# ShoulderDriverChannel.net
KiCad netlist of a schematic drawn in Altium Designer
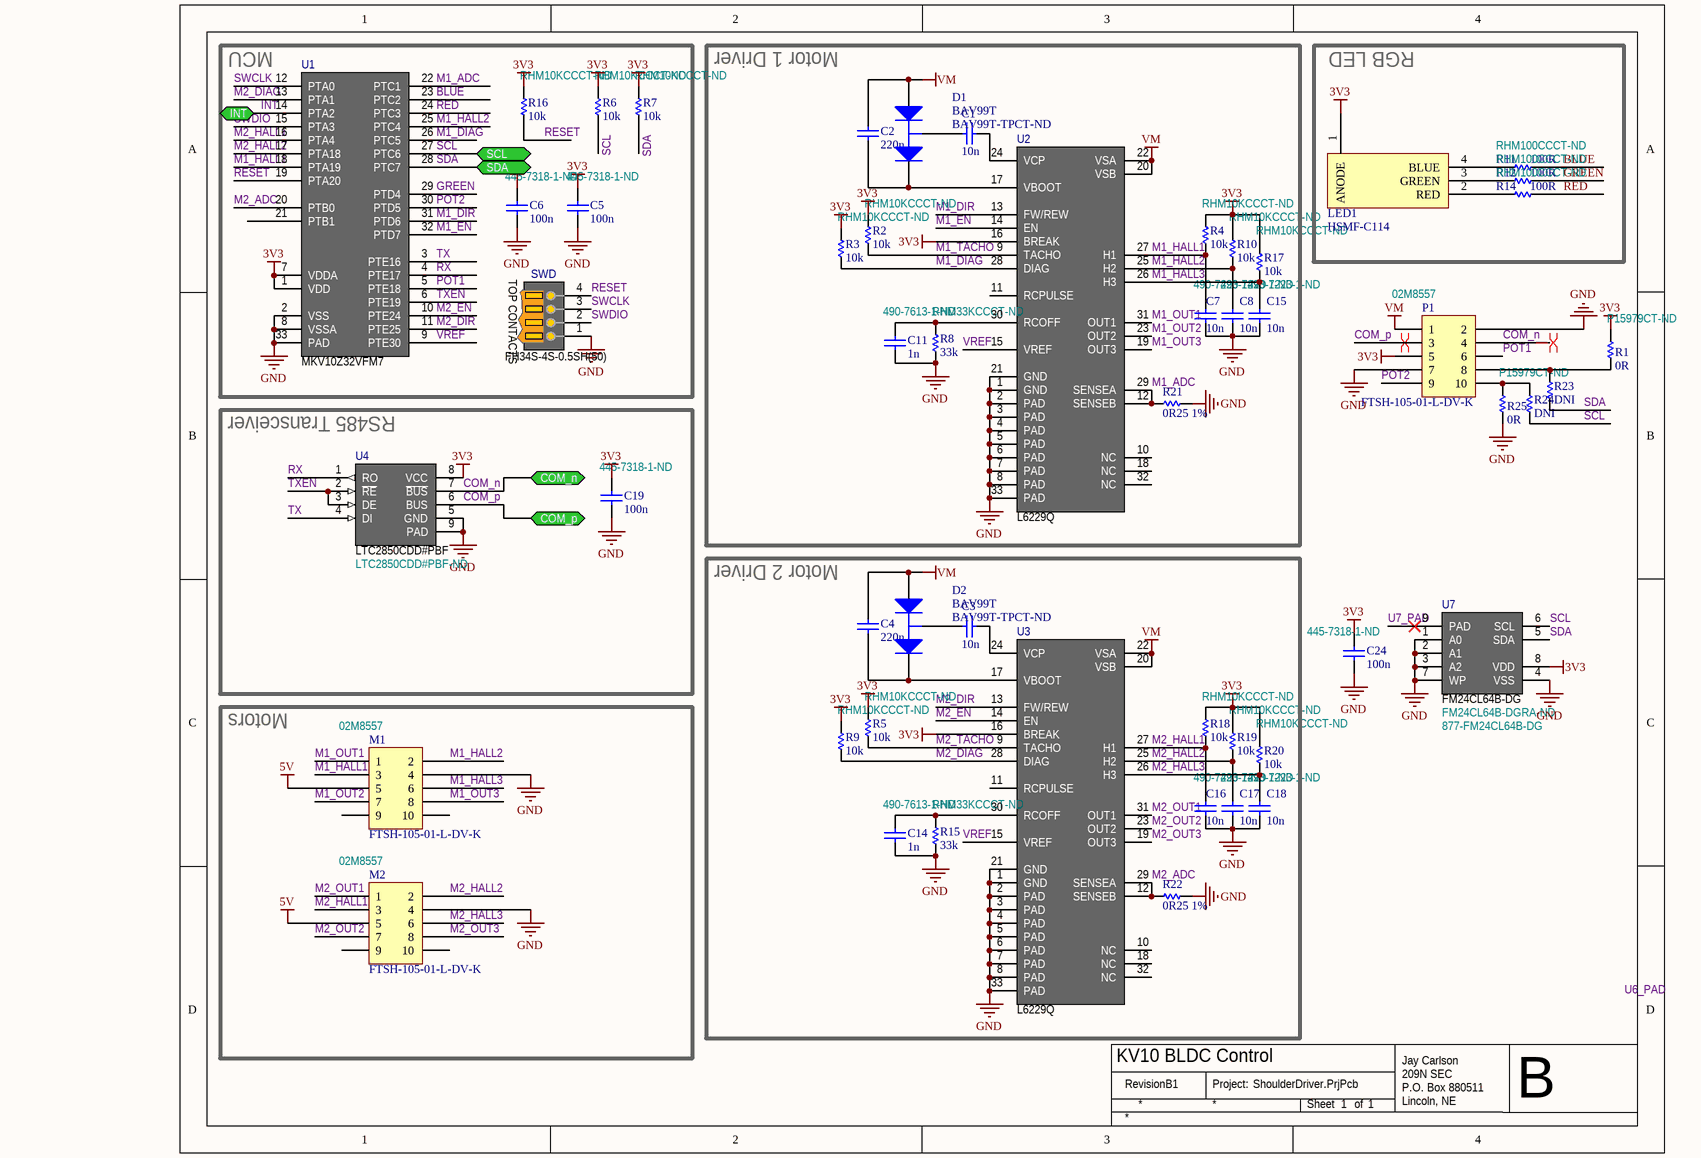
[diagram p0: ShoulderDriverChannel.SchDoc]

(export (version "E")
  (design (tool "Eeschema 10.0.6"))
  (components
    (comp (ref "C1")
      (value "10n")
      (footprint "CAPC1005N")
      (description "Capacitor (Semiconductor SIM Model)")
      (fields (field (name "PUBLISHER") "Altium Limited"))
      (libsource (lib "Miscellaneous Devices") (part "Cap Semi"))
    )
    (comp (ref "C2")
      (value "220n")
      (footprint "CAPC1005N")
      (description "Capacitor (Semiconductor SIM Model)")
      (fields (field (name "PUBLISHER") "Altium Limited"))
      (libsource (lib "Miscellaneous Devices") (part "Cap Semi"))
    )
    (comp (ref "C3")
      (value "10n")
      (footprint "CAPC1005N")
      (description "Capacitor (Semiconductor SIM Model)")
      (fields (field (name "PUBLISHER") "Altium Limited"))
      (libsource (lib "Miscellaneous Devices") (part "Cap Semi"))
    )
    (comp (ref "C4")
      (value "220n")
      (footprint "CAPC1005N")
      (description "Capacitor (Semiconductor SIM Model)")
      (fields (field (name "PUBLISHER") "Altium Limited"))
      (libsource (lib "Miscellaneous Devices") (part "Cap Semi"))
    )
    (comp (ref "C5")
      (value "100n")
      (footprint "CAPC0603N")
      (description "Capacitor (Semiconductor SIM Model)")
      (fields
        (field (name "SUPPLIER PART NUMBER 1") "445-7318-1-ND")
        (field (name "PUBLISHER") "Altium Limited")
      )
      (libsource (lib "Miscellaneous Devices") (part "Cap Semi"))
    )
    (comp (ref "C6")
      (value "100n")
      (footprint "CAPC0603N")
      (description "Capacitor (Semiconductor SIM Model)")
      (fields
        (field (name "SUPPLIER PART NUMBER 1") "445-7318-1-ND")
        (field (name "PUBLISHER") "Altium Limited")
      )
      (libsource (lib "Miscellaneous Devices") (part "Cap Semi"))
    )
    (comp (ref "C7")
      (value "10n")
      (footprint "CAPC0603N")
      (description "Capacitor (Semiconductor SIM Model)")
      (fields
        (field (name "SUPPLIER PART NUMBER 1") "490-7223-1-ND")
        (field (name "PUBLISHER") "Altium Limited")
      )
      (libsource (lib "Miscellaneous Devices") (part "Cap Semi"))
    )
    (comp (ref "C8")
      (value "10n")
      (footprint "CAPC0603N")
      (description "Capacitor (Semiconductor SIM Model)")
      (fields
        (field (name "SUPPLIER PART NUMBER 1") "490-7223-1-ND")
        (field (name "PUBLISHER") "Altium Limited")
      )
      (libsource (lib "Miscellaneous Devices") (part "Cap Semi"))
    )
    (comp (ref "C11")
      (value "1n")
      (footprint "CAPC0603N")
      (description "Capacitor (Semiconductor SIM Model)")
      (fields
        (field (name "SUPPLIER PART NUMBER 1") "490-7613-1-ND")
        (field (name "PUBLISHER") "Altium Limited")
      )
      (libsource (lib "Miscellaneous Devices") (part "Cap Semi"))
    )
    (comp (ref "C14")
      (value "1n")
      (footprint "CAPC0603N")
      (description "Capacitor (Semiconductor SIM Model)")
      (fields
        (field (name "SUPPLIER PART NUMBER 1") "490-7613-1-ND")
        (field (name "PUBLISHER") "Altium Limited")
      )
      (libsource (lib "Miscellaneous Devices") (part "Cap Semi"))
    )
    (comp (ref "C15")
      (value "10n")
      (footprint "CAPC0603N")
      (description "Capacitor (Semiconductor SIM Model)")
      (fields
        (field (name "SUPPLIER PART NUMBER 1") "490-7223-1-ND")
        (field (name "PUBLISHER") "Altium Limited")
      )
      (libsource (lib "Miscellaneous Devices") (part "Cap Semi"))
    )
    (comp (ref "C16")
      (value "10n")
      (footprint "CAPC0603N")
      (description "Capacitor (Semiconductor SIM Model)")
      (fields
        (field (name "SUPPLIER PART NUMBER 1") "490-7223-1-ND")
        (field (name "PUBLISHER") "Altium Limited")
      )
      (libsource (lib "Miscellaneous Devices") (part "Cap Semi"))
    )
    (comp (ref "C17")
      (value "10n")
      (footprint "CAPC0603N")
      (description "Capacitor (Semiconductor SIM Model)")
      (fields
        (field (name "SUPPLIER PART NUMBER 1") "490-7223-1-ND")
        (field (name "PUBLISHER") "Altium Limited")
      )
      (libsource (lib "Miscellaneous Devices") (part "Cap Semi"))
    )
    (comp (ref "C18")
      (value "10n")
      (footprint "CAPC0603N")
      (description "Capacitor (Semiconductor SIM Model)")
      (fields
        (field (name "SUPPLIER PART NUMBER 1") "490-7223-1-ND")
        (field (name "PUBLISHER") "Altium Limited")
      )
      (libsource (lib "Miscellaneous Devices") (part "Cap Semi"))
    )
    (comp (ref "C19")
      (value "100n")
      (footprint "CAPC0603N")
      (description "Capacitor (Semiconductor SIM Model)")
      (fields
        (field (name "SUPPLIER PART NUMBER 1") "445-7318-1-ND")
        (field (name "PUBLISHER") "Altium Limited")
      )
      (libsource (lib "Miscellaneous Devices") (part "Cap Semi"))
    )
    (comp (ref "C24")
      (value "100n")
      (footprint "CAPC0603N")
      (description "Capacitor (Semiconductor SIM Model)")
      (fields
        (field (name "SUPPLIER PART NUMBER 1") "445-7318-1-ND")
        (field (name "PUBLISHER") "Altium Limited")
      )
      (libsource (lib "Miscellaneous Devices") (part "Cap Semi"))
    )
    (comp (ref "D1")
      (value "BAV99T")
      (footprint "SOT-523 (SC-75)")
      (description "Silicon Switching Diode for High-Speed Switching")
      (fields
        (field (name "SUPPLIER PART NUMBER 1") "BAV99T-TPCT-ND")
        (field (name "PUBLISHER") "Altium Limited")
      )
      (libsource (lib "Infineon Discrete Diode") (part "BAV99T"))
    )
    (comp (ref "D2")
      (value "BAV99T")
      (footprint "SOT-523 (SC-75)")
      (description "Silicon Switching Diode for High-Speed Switching")
      (fields
        (field (name "SUPPLIER PART NUMBER 1") "BAV99T-TPCT-ND")
        (field (name "PUBLISHER") "Altium Limited")
      )
      (libsource (lib "Infineon Discrete Diode") (part "BAV99T"))
    )
    (comp (ref "LED1")
      (value "HSMF-C114")
      (footprint "HSMF-C114")
      (description "LED CHIP RGB 1.6X1.5X0.35MM SMD")
      (fields (field (name "MANUFACTURER") "Avago Technologies US Inc."))
      (libsource (lib "components") (part "HSMF-C114"))
    )
    (comp (ref "M1")
      (value "FTSH-105-01-L-DV-K")
      (footprint "FTSH-105-01-L-DV-K")
      (description "Header, 5-Pin, Dual row")
      (fields (field (name "SUPPLIER PART NUMBER 1") "02M8557") (field (name "PUBLISHER") "Altium Limited"))
      (libsource (lib "Miscellaneous Connectors") (part "MHDR2X5"))
    )
    (comp (ref "M2")
      (value "FTSH-105-01-L-DV-K")
      (footprint "FTSH-105-01-L-DV-K")
      (description "Header, 5-Pin, Dual row")
      (fields (field (name "SUPPLIER PART NUMBER 1") "02M8557") (field (name "PUBLISHER") "Altium Limited"))
      (libsource (lib "Miscellaneous Connectors") (part "MHDR2X5"))
    )
    (comp (ref "P1")
      (value "FTSH-105-01-L-DV-K")
      (footprint "FTSH-105-01-L-DV-K")
      (description "Header, 5-Pin, Dual row")
      (fields (field (name "SUPPLIER PART NUMBER 1") "02M8557") (field (name "PUBLISHER") "Altium Limited"))
      (libsource (lib "Miscellaneous Connectors") (part "MHDR2X5"))
    )
    (comp (ref "R1")
      (value "0R")
      (footprint "RESC0603N")
      (description "Semiconductor Resistor")
      (fields
        (field (name "SUPPLIER PART NUMBER 1") "P15979CT-ND")
        (field (name "PUBLISHER") "Altium Limited")
      )
      (libsource (lib "Miscellaneous Devices") (part "Res Semi"))
    )
    (comp (ref "R2")
      (value "10k")
      (footprint "RESC0603N")
      (description "Semiconductor Resistor")
      (fields
        (field (name "SUPPLIER PART NUMBER 1") "RHM10KCCCT-ND")
        (field (name "PUBLISHER") "Altium Limited")
      )
      (libsource (lib "Miscellaneous Devices") (part "Res Semi"))
    )
    (comp (ref "R3")
      (value "10k")
      (footprint "RESC0603N")
      (description "Semiconductor Resistor")
      (fields
        (field (name "SUPPLIER PART NUMBER 1") "RHM10KCCCT-ND")
        (field (name "PUBLISHER") "Altium Limited")
      )
      (libsource (lib "Miscellaneous Devices") (part "Res Semi"))
    )
    (comp (ref "R4")
      (value "10k")
      (footprint "RESC0603N")
      (description "Semiconductor Resistor")
      (fields
        (field (name "SUPPLIER PART NUMBER 1") "RHM10KCCCT-ND")
        (field (name "PUBLISHER") "Altium Limited")
      )
      (libsource (lib "Miscellaneous Devices") (part "Res Semi"))
    )
    (comp (ref "R5")
      (value "10k")
      (footprint "RESC0603N")
      (description "Semiconductor Resistor")
      (fields
        (field (name "SUPPLIER PART NUMBER 1") "RHM10KCCCT-ND")
        (field (name "PUBLISHER") "Altium Limited")
      )
      (libsource (lib "Miscellaneous Devices") (part "Res Semi"))
    )
    (comp (ref "R6")
      (value "10k")
      (footprint "RESC0603N")
      (description "Semiconductor Resistor")
      (fields
        (field (name "SUPPLIER PART NUMBER 1") "RHM10KCCCT-ND")
        (field (name "PUBLISHER") "Altium Limited")
      )
      (libsource (lib "Miscellaneous Devices") (part "Res Semi"))
    )
    (comp (ref "R7")
      (value "10k")
      (footprint "RESC0603N")
      (description "Semiconductor Resistor")
      (fields
        (field (name "SUPPLIER PART NUMBER 1") "RHM10KCCCT-ND")
        (field (name "PUBLISHER") "Altium Limited")
      )
      (libsource (lib "Miscellaneous Devices") (part "Res Semi"))
    )
    (comp (ref "R8")
      (value "33k")
      (footprint "RESC0603N")
      (description "Semiconductor Resistor")
      (fields
        (field (name "SUPPLIER PART NUMBER 1") "RHM33KCCCT-ND")
        (field (name "PUBLISHER") "Altium Limited")
      )
      (libsource (lib "Miscellaneous Devices") (part "Res Semi"))
    )
    (comp (ref "R9")
      (value "10k")
      (footprint "RESC0603N")
      (description "Semiconductor Resistor")
      (fields
        (field (name "SUPPLIER PART NUMBER 1") "RHM10KCCCT-ND")
        (field (name "PUBLISHER") "Altium Limited")
      )
      (libsource (lib "Miscellaneous Devices") (part "Res Semi"))
    )
    (comp (ref "R10")
      (value "10k")
      (footprint "RESC0603N")
      (description "Semiconductor Resistor")
      (fields
        (field (name "SUPPLIER PART NUMBER 1") "RHM10KCCCT-ND")
        (field (name "PUBLISHER") "Altium Limited")
      )
      (libsource (lib "Miscellaneous Devices") (part "Res Semi"))
    )
    (comp (ref "R11")
      (value "100R")
      (footprint "RESC0603N")
      (description "Semiconductor Resistor")
      (fields
        (field (name "SUPPLIER PART NUMBER 1") "RHM100CCCT-ND")
        (field (name "PUBLISHER") "Altium Limited")
      )
      (libsource (lib "Miscellaneous Devices") (part "Res Semi"))
    )
    (comp (ref "R12")
      (value "100R")
      (footprint "RESC0603N")
      (description "Semiconductor Resistor")
      (fields
        (field (name "SUPPLIER PART NUMBER 1") "RHM100CCCT-ND")
        (field (name "PUBLISHER") "Altium Limited")
      )
      (libsource (lib "Miscellaneous Devices") (part "Res Semi"))
    )
    (comp (ref "R14")
      (value "100R")
      (footprint "RESC0603N")
      (description "Semiconductor Resistor")
      (fields
        (field (name "SUPPLIER PART NUMBER 1") "RHM100CCCT-ND")
        (field (name "PUBLISHER") "Altium Limited")
      )
      (libsource (lib "Miscellaneous Devices") (part "Res Semi"))
    )
    (comp (ref "R15")
      (value "33k")
      (footprint "RESC0603N")
      (description "Semiconductor Resistor")
      (fields
        (field (name "SUPPLIER PART NUMBER 1") "RHM33KCCCT-ND")
        (field (name "PUBLISHER") "Altium Limited")
      )
      (libsource (lib "Miscellaneous Devices") (part "Res Semi"))
    )
    (comp (ref "R16")
      (value "10k")
      (footprint "RESC0603N")
      (description "Semiconductor Resistor")
      (fields
        (field (name "SUPPLIER PART NUMBER 1") "RHM10KCCCT-ND")
        (field (name "PUBLISHER") "Altium Limited")
      )
      (libsource (lib "Miscellaneous Devices") (part "Res Semi"))
    )
    (comp (ref "R17")
      (value "10k")
      (footprint "RESC0603N")
      (description "Semiconductor Resistor")
      (fields
        (field (name "SUPPLIER PART NUMBER 1") "RHM10KCCCT-ND")
        (field (name "PUBLISHER") "Altium Limited")
      )
      (libsource (lib "Miscellaneous Devices") (part "Res Semi"))
    )
    (comp (ref "R18")
      (value "10k")
      (footprint "RESC0603N")
      (description "Semiconductor Resistor")
      (fields
        (field (name "SUPPLIER PART NUMBER 1") "RHM10KCCCT-ND")
        (field (name "PUBLISHER") "Altium Limited")
      )
      (libsource (lib "Miscellaneous Devices") (part "Res Semi"))
    )
    (comp (ref "R19")
      (value "10k")
      (footprint "RESC0603N")
      (description "Semiconductor Resistor")
      (fields
        (field (name "SUPPLIER PART NUMBER 1") "RHM10KCCCT-ND")
        (field (name "PUBLISHER") "Altium Limited")
      )
      (libsource (lib "Miscellaneous Devices") (part "Res Semi"))
    )
    (comp (ref "R20")
      (value "10k")
      (footprint "RESC0603N")
      (description "Semiconductor Resistor")
      (fields
        (field (name "SUPPLIER PART NUMBER 1") "RHM10KCCCT-ND")
        (field (name "PUBLISHER") "Altium Limited")
      )
      (libsource (lib "Miscellaneous Devices") (part "Res Semi"))
    )
    (comp (ref "R21")
      (value "0R25 1%")
      (footprint "RESC1608N")
      (description "Semiconductor Resistor")
      (fields (field (name "PUBLISHER") "Altium Limited"))
      (libsource (lib "Miscellaneous Devices") (part "Res Semi"))
    )
    (comp (ref "R22")
      (value "0R25 1%")
      (footprint "RESC1608N")
      (description "Semiconductor Resistor")
      (fields (field (name "PUBLISHER") "Altium Limited"))
      (libsource (lib "Miscellaneous Devices") (part "Res Semi"))
    )
    (comp (ref "R23")
      (value "DNI")
      (footprint "RESC0603N")
      (description "Semiconductor Resistor")
      (fields (field (name "PUBLISHER") "Altium Limited"))
      (libsource (lib "Miscellaneous Devices") (part "Res Semi"))
    )
    (comp (ref "R24")
      (value "DNI")
      (footprint "RESC0603N")
      (description "Semiconductor Resistor")
      (fields (field (name "PUBLISHER") "Altium Limited"))
      (libsource (lib "Miscellaneous Devices") (part "Res Semi"))
    )
    (comp (ref "R25")
      (value "0R")
      (footprint "RESC0603N")
      (description "Semiconductor Resistor")
      (fields
        (field (name "SUPPLIER PART NUMBER 1") "P15979CT-ND")
        (field (name "PUBLISHER") "Altium Limited")
      )
      (libsource (lib "Miscellaneous Devices") (part "Res Semi"))
    )
    (comp (ref "SWD")
      (value "FH34S-4S-0.5SH(50)")
      (footprint "FH34S-4S-0.5SH(50)")
      (description "CONN FPC/FFC 4POS .5MM SMD GOLD")
      (fields (field (name "MANUFACTURER") "Hirose Electric Co Ltd"))
      (libsource (lib "FH34 series") (part "FH34S-4S-0.5SH(50)"))
    )
    (comp (ref "U1")
      (value "MKV10Z32VFM7")
      (footprint "QFN50P500X500-32V2N")
      (description "Kinetis Cortex-M0+75 MHz Motor Control 32QFN")
      (fields (field (name "MANUFACTURER") "Freescale Semiconductor"))
      (libsource (lib "Freescale K-Series ARM Microcontroller") (part "MKV10Z32VFM7"))
    )
    (comp (ref "U2")
      (value "L6229Q")
      (footprint "L6229Q")
      (description "IC MOTOR DRIVER PAR 32VFQFPN")
      (fields
        (field (name "MANUFACTURER") "STMicroelectronics")
        (field (name "MANUFACTURER PART NUMBER") "L6229QTR")
      )
      (libsource (lib "ST Motor Driver") (part "L6229Q"))
    )
    (comp (ref "U3")
      (value "L6229Q")
      (footprint "L6229Q")
      (description "IC MOTOR DRIVER PAR 32VFQFPN")
      (fields
        (field (name "MANUFACTURER") "STMicroelectronics")
        (field (name "MANUFACTURER PART NUMBER") "L6229QTR")
      )
      (libsource (lib "ST Motor Driver") (part "L6229Q"))
    )
    (comp (ref "U4")
      (value "LTC2850CDD#PBF")
      (footprint "DFN50P300X300X75-8N")
      (description "IC TXRX RS485 20MBPS 8-DFN")
      (fields
        (field (name "MANUFACTURER") "Linear Technology")
        (field (name "MANUFACTURER PART NUMBER") "LTC2850CMS8#PBF")
        (field (name "SUPPLIER PART NUMBER 1") "LTC2850CDD#PBF-ND")
      )
      (libsource (lib "LTC Transceiver") (part "LTC2850CDD#PBF"))
    )
    (comp (ref "U7")
      (value "FM24CL64B-DG")
      (footprint "DFN95P400X445X80_HS-9N")
      (description "IC FRAM 64KBIT 1MHZ 8TDFN")
      (fields
        (field (name "MANUFACTURER") "Cypress Semiconductor Corp")
        (field (name "SUPPLIER PART NUMBER 1") "FM24CL64B-DGRA-ND")
        (field (name "SUPPLIER PART NUMBER 2") "877-FM24CL64B-DG")
      )
      (libsource (lib "Cypress FRAM") (part "FM24CL64B-DG"))
    )
  )
  (nets
    (net (code "1") (name "/BLUE") (class "Default")
      (node (ref "R11") (pin "1") (pinfunction "1_1") (pintype "passive"))
      (node (ref "U1") (pin "23") (pinfunction "PTC2_23") (pintype "passive"))
    )
    (net (code "2") (name "/COM_n") (class "Default")
      (node (ref "P1") (pin "4") (pinfunction "4_4") (pintype "passive"))
      (node (ref "U4") (pin "7") (pinfunction "~{BUS}_7") (pintype "power_in"))
    )
    (net (code "3") (name "/COM_p") (class "Default")
      (node (ref "P1") (pin "3") (pinfunction "3_3") (pintype "passive"))
      (node (ref "U4") (pin "6") (pinfunction "BUS_6") (pintype "power_in"))
    )
    (net (code "4") (name "/GREEN") (class "Default")
      (node (ref "R12") (pin "1") (pinfunction "1_1") (pintype "passive"))
      (node (ref "U1") (pin "29") (pinfunction "PTD4_29") (pintype "passive"))
    )
    (net (code "5") (name "/INT") (class "Default")
      (node (ref "U1") (pin "14") (pinfunction "PTA2_14") (pintype "passive"))
    )
    (net (code "6") (name "/M1_ADC") (class "Default")
      (node (ref "R21") (pin "2") (pinfunction "2_2") (pintype "passive"))
      (node (ref "U1") (pin "22") (pinfunction "PTC1_22") (pintype "passive"))
      (node (ref "U2") (pin "12") (pinfunction "SENSEB_12") (pintype "passive"))
      (node (ref "U2") (pin "29") (pinfunction "SENSEA_29") (pintype "passive"))
    )
    (net (code "7") (name "/M1_DIAG") (class "Default")
      (node (ref "R3") (pin "2") (pinfunction "2_2") (pintype "passive"))
      (node (ref "U1") (pin "26") (pinfunction "PTC5_26") (pintype "passive"))
      (node (ref "U2") (pin "28") (pinfunction "DIAG_28") (pintype "passive"))
    )
    (net (code "8") (name "/M1_DIR") (class "Default")
      (node (ref "U1") (pin "31") (pinfunction "PTD6_31") (pintype "passive"))
      (node (ref "U2") (pin "13") (pinfunction "FW/REW_13") (pintype "passive"))
    )
    (net (code "9") (name "/M1_EN") (class "Default")
      (node (ref "U1") (pin "32") (pinfunction "PTD7_32") (pintype "passive"))
      (node (ref "U2") (pin "14") (pinfunction "EN_14") (pintype "passive"))
    )
    (net (code "10") (name "/M1_HALL1") (class "Default")
      (node (ref "C7") (pin "2") (pinfunction "2_2") (pintype "passive"))
      (node (ref "M1") (pin "3") (pinfunction "3_3") (pintype "passive"))
      (node (ref "R4") (pin "1") (pinfunction "1_1") (pintype "passive"))
      (node (ref "U1") (pin "18") (pinfunction "PTA19_18") (pintype "passive"))
      (node (ref "U2") (pin "27") (pinfunction "H1_27") (pintype "passive"))
    )
    (net (code "11") (name "/M1_HALL2") (class "Default")
      (node (ref "C8") (pin "2") (pinfunction "2_2") (pintype "passive"))
      (node (ref "M1") (pin "2") (pinfunction "2_2") (pintype "passive"))
      (node (ref "R10") (pin "1") (pinfunction "1_1") (pintype "passive"))
      (node (ref "U1") (pin "25") (pinfunction "PTC4_25") (pintype "passive"))
      (node (ref "U2") (pin "25") (pinfunction "H2_25") (pintype "passive"))
    )
    (net (code "12") (name "/M1_HALL3") (class "Default")
      (node (ref "C15") (pin "2") (pinfunction "2_2") (pintype "passive"))
      (node (ref "M1") (pin "6") (pinfunction "6_6") (pintype "passive"))
      (node (ref "R17") (pin "1") (pinfunction "1_1") (pintype "passive"))
      (node (ref "U2") (pin "26") (pinfunction "H3_26") (pintype "passive"))
    )
    (net (code "13") (name "/M1_OUT1") (class "Default")
      (node (ref "M1") (pin "1") (pinfunction "1_1") (pintype "passive"))
      (node (ref "U2") (pin "31") (pinfunction "OUT1_31") (pintype "passive"))
    )
    (net (code "14") (name "/M1_OUT2") (class "Default")
      (node (ref "M1") (pin "7") (pinfunction "7_7") (pintype "passive"))
      (node (ref "U2") (pin "23") (pinfunction "OUT2_23") (pintype "passive"))
    )
    (net (code "15") (name "/M1_OUT3") (class "Default")
      (node (ref "M1") (pin "8") (pinfunction "8_8") (pintype "passive"))
      (node (ref "U2") (pin "19") (pinfunction "OUT3_19") (pintype "passive"))
    )
    (net (code "16") (name "/M1_TACHO") (class "Default")
      (node (ref "R2") (pin "2") (pinfunction "2_2") (pintype "passive"))
      (node (ref "U2") (pin "9") (pinfunction "TACHO_9") (pintype "passive"))
    )
    (net (code "17") (name "/M2_ADC") (class "Default")
      (node (ref "R22") (pin "2") (pinfunction "2_2") (pintype "passive"))
      (node (ref "U1") (pin "20") (pinfunction "PTB0_20") (pintype "passive"))
      (node (ref "U3") (pin "12") (pinfunction "SENSEB_12") (pintype "passive"))
      (node (ref "U3") (pin "29") (pinfunction "SENSEA_29") (pintype "passive"))
    )
    (net (code "18") (name "/M2_DIAG") (class "Default")
      (node (ref "R9") (pin "2") (pinfunction "2_2") (pintype "passive"))
      (node (ref "U1") (pin "13") (pinfunction "PTA1_13") (pintype "passive"))
      (node (ref "U3") (pin "28") (pinfunction "DIAG_28") (pintype "passive"))
    )
    (net (code "19") (name "/M2_DIR") (class "Default")
      (node (ref "U1") (pin "11") (pinfunction "PTE25_11") (pintype "passive"))
      (node (ref "U3") (pin "13") (pinfunction "FW/REW_13") (pintype "passive"))
    )
    (net (code "20") (name "/M2_EN") (class "Default")
      (node (ref "U1") (pin "10") (pinfunction "PTE24_10") (pintype "passive"))
      (node (ref "U3") (pin "14") (pinfunction "EN_14") (pintype "passive"))
    )
    (net (code "21") (name "/M2_HALL1") (class "Default")
      (node (ref "C16") (pin "2") (pinfunction "2_2") (pintype "passive"))
      (node (ref "M2") (pin "3") (pinfunction "3_3") (pintype "passive"))
      (node (ref "R18") (pin "1") (pinfunction "1_1") (pintype "passive"))
      (node (ref "U1") (pin "16") (pinfunction "PTA4_16") (pintype "passive"))
      (node (ref "U3") (pin "27") (pinfunction "H1_27") (pintype "passive"))
    )
    (net (code "22") (name "/M2_HALL2") (class "Default")
      (node (ref "C17") (pin "2") (pinfunction "2_2") (pintype "passive"))
      (node (ref "M2") (pin "2") (pinfunction "2_2") (pintype "passive"))
      (node (ref "R19") (pin "1") (pinfunction "1_1") (pintype "passive"))
      (node (ref "U1") (pin "17") (pinfunction "PTA18_17") (pintype "passive"))
      (node (ref "U3") (pin "25") (pinfunction "H2_25") (pintype "passive"))
    )
    (net (code "23") (name "/M2_HALL3") (class "Default")
      (node (ref "C18") (pin "2") (pinfunction "2_2") (pintype "passive"))
      (node (ref "M2") (pin "6") (pinfunction "6_6") (pintype "passive"))
      (node (ref "R20") (pin "1") (pinfunction "1_1") (pintype "passive"))
      (node (ref "U3") (pin "26") (pinfunction "H3_26") (pintype "passive"))
    )
    (net (code "24") (name "/M2_OUT1") (class "Default")
      (node (ref "M2") (pin "1") (pinfunction "1_1") (pintype "passive"))
      (node (ref "U3") (pin "31") (pinfunction "OUT1_31") (pintype "passive"))
    )
    (net (code "25") (name "/M2_OUT2") (class "Default")
      (node (ref "M2") (pin "7") (pinfunction "7_7") (pintype "passive"))
      (node (ref "U3") (pin "23") (pinfunction "OUT2_23") (pintype "passive"))
    )
    (net (code "26") (name "/M2_OUT3") (class "Default")
      (node (ref "M2") (pin "8") (pinfunction "8_8") (pintype "passive"))
      (node (ref "U3") (pin "19") (pinfunction "OUT3_19") (pintype "passive"))
    )
    (net (code "27") (name "/M2_TACHO") (class "Default")
      (node (ref "R5") (pin "2") (pinfunction "2_2") (pintype "passive"))
      (node (ref "U3") (pin "9") (pinfunction "TACHO_9") (pintype "passive"))
    )
    (net (code "28") (name "/POT1") (class "Default")
      (node (ref "P1") (pin "6") (pinfunction "6_6") (pintype "passive"))
      (node (ref "U1") (pin "5") (pinfunction "PTE18_5") (pintype "passive"))
    )
    (net (code "29") (name "/POT2") (class "Default")
      (node (ref "P1") (pin "9") (pinfunction "9_9") (pintype "passive"))
      (node (ref "U1") (pin "30") (pinfunction "PTD5_30") (pintype "passive"))
    )
    (net (code "30") (name "/RED") (class "Default")
      (node (ref "R14") (pin "1") (pinfunction "1_1") (pintype "passive"))
      (node (ref "U1") (pin "24") (pinfunction "PTC3_24") (pintype "passive"))
    )
    (net (code "31") (name "/RESET") (class "Default")
      (node (ref "R16") (pin "1") (pinfunction "1_1") (pintype "passive"))
      (node (ref "SWD") (pin "4") (pinfunction "4_4") (pintype "passive"))
      (node (ref "U1") (pin "19") (pinfunction "PTA20_19") (pintype "passive"))
    )
    (net (code "32") (name "/RX") (class "Default")
      (node (ref "U1") (pin "4") (pinfunction "PTE17_4") (pintype "passive"))
      (node (ref "U4") (pin "1") (pinfunction "RO_1") (pintype "output"))
    )
    (net (code "33") (name "/SCL") (class "Default")
      (node (ref "R24") (pin "2") (pinfunction "2_2") (pintype "passive"))
      (node (ref "R6") (pin "1") (pinfunction "1_1") (pintype "passive"))
      (node (ref "U1") (pin "27") (pinfunction "PTC6_27") (pintype "passive"))
      (node (ref "U7") (pin "6") (pinfunction "SCL_6") (pintype "power_in"))
    )
    (net (code "34") (name "/SDA") (class "Default")
      (node (ref "R23") (pin "2") (pinfunction "2_2") (pintype "passive"))
      (node (ref "R7") (pin "1") (pinfunction "1_1") (pintype "passive"))
      (node (ref "U1") (pin "28") (pinfunction "PTC7_28") (pintype "passive"))
      (node (ref "U7") (pin "5") (pinfunction "SDA_5") (pintype "power_in"))
    )
    (net (code "35") (name "/SWCLK") (class "Default")
      (node (ref "SWD") (pin "3") (pinfunction "3_3") (pintype "passive"))
      (node (ref "U1") (pin "12") (pinfunction "PTA0_12") (pintype "passive"))
    )
    (net (code "36") (name "/SWDIO") (class "Default")
      (node (ref "SWD") (pin "2") (pinfunction "2_2") (pintype "passive"))
      (node (ref "U1") (pin "15") (pinfunction "PTA3_15") (pintype "passive"))
    )
    (net (code "37") (name "/TX") (class "Default")
      (node (ref "U1") (pin "3") (pinfunction "PTE16_3") (pintype "passive"))
      (node (ref "U4") (pin "4") (pinfunction "DI_4") (pintype "input"))
    )
    (net (code "38") (name "/TXEN") (class "Default")
      (node (ref "U1") (pin "6") (pinfunction "PTE19_6") (pintype "passive"))
      (node (ref "U4") (pin "2") (pinfunction "~{RE}_2") (pintype "input"))
      (node (ref "U4") (pin "3") (pinfunction "DE_3") (pintype "input"))
    )
    (net (code "40") (name "/U7_PAD") (class "Default")
      (node (ref "U7") (pin "9") (pinfunction "PAD_9") (pintype "power_in+no_connect"))
    )
    (net (code "41") (name "/VREF") (class "Default")
      (node (ref "U1") (pin "9") (pinfunction "PTE30_9") (pintype "passive"))
      (node (ref "U2") (pin "15") (pinfunction "VREF_15") (pintype "passive"))
      (node (ref "U3") (pin "15") (pinfunction "VREF_15") (pintype "passive"))
    )
    (net (code "42") (name "3V3") (class "Default")
      (node (ref "C19") (pin "2") (pinfunction "2_2") (pintype "passive"))
      (node (ref "C24") (pin "2") (pinfunction "2_2") (pintype "passive"))
      (node (ref "C5") (pin "2") (pinfunction "2_2") (pintype "passive"))
      (node (ref "C6") (pin "2") (pinfunction "2_2") (pintype "passive"))
      (node (ref "LED1") (pin "1") (pinfunction "ANODE_1") (pintype "passive"))
      (node (ref "P1") (pin "5") (pinfunction "5_5") (pintype "passive"))
      (node (ref "R1") (pin "2") (pinfunction "2_2") (pintype "passive"))
      (node (ref "R10") (pin "2") (pinfunction "2_2") (pintype "passive"))
      (node (ref "R16") (pin "2") (pinfunction "2_2") (pintype "passive"))
      (node (ref "R17") (pin "2") (pinfunction "2_2") (pintype "passive"))
      (node (ref "R18") (pin "2") (pinfunction "2_2") (pintype "passive"))
      (node (ref "R19") (pin "2") (pinfunction "2_2") (pintype "passive"))
      (node (ref "R2") (pin "1") (pinfunction "1_1") (pintype "passive"))
      (node (ref "R20") (pin "2") (pinfunction "2_2") (pintype "passive"))
      (node (ref "R3") (pin "1") (pinfunction "1_1") (pintype "passive"))
      (node (ref "R4") (pin "2") (pinfunction "2_2") (pintype "passive"))
      (node (ref "R5") (pin "1") (pinfunction "1_1") (pintype "passive"))
      (node (ref "R6") (pin "2") (pinfunction "2_2") (pintype "passive"))
      (node (ref "R7") (pin "2") (pinfunction "2_2") (pintype "passive"))
      (node (ref "R9") (pin "1") (pinfunction "1_1") (pintype "passive"))
      (node (ref "U1") (pin "1") (pinfunction "VDD_1") (pintype "passive"))
      (node (ref "U1") (pin "7") (pinfunction "VDDA_7") (pintype "passive"))
      (node (ref "U2") (pin "16") (pinfunction "BREAK_16") (pintype "passive"))
      (node (ref "U3") (pin "16") (pinfunction "BREAK_16") (pintype "passive"))
      (node (ref "U4") (pin "8") (pinfunction "VCC_8") (pintype "power_in"))
      (node (ref "U7") (pin "8") (pinfunction "VDD_8") (pintype "power_in"))
    )
    (net (code "43") (name "5V") (class "Default")
      (node (ref "M1") (pin "5") (pinfunction "5_5") (pintype "passive"))
      (node (ref "M2") (pin "5") (pinfunction "5_5") (pintype "passive"))
    )
    (net (code "44") (name "GND") (class "Default")
      (node (ref "C11") (pin "1") (pinfunction "1_1") (pintype "passive"))
      (node (ref "C14") (pin "1") (pinfunction "1_1") (pintype "passive"))
      (node (ref "C15") (pin "1") (pinfunction "1_1") (pintype "passive"))
      (node (ref "C16") (pin "1") (pinfunction "1_1") (pintype "passive"))
      (node (ref "C17") (pin "1") (pinfunction "1_1") (pintype "passive"))
      (node (ref "C18") (pin "1") (pinfunction "1_1") (pintype "passive"))
      (node (ref "C19") (pin "1") (pinfunction "1_1") (pintype "passive"))
      (node (ref "C24") (pin "1") (pinfunction "1_1") (pintype "passive"))
      (node (ref "C5") (pin "1") (pinfunction "1_1") (pintype "passive"))
      (node (ref "C6") (pin "1") (pinfunction "1_1") (pintype "passive"))
      (node (ref "C7") (pin "1") (pinfunction "1_1") (pintype "passive"))
      (node (ref "C8") (pin "1") (pinfunction "1_1") (pintype "passive"))
      (node (ref "M1") (pin "4") (pinfunction "4_4") (pintype "passive"))
      (node (ref "M2") (pin "4") (pinfunction "4_4") (pintype "passive"))
      (node (ref "P1") (pin "2") (pinfunction "2_2") (pintype "passive"))
      (node (ref "P1") (pin "7") (pinfunction "7_7") (pintype "passive"))
      (node (ref "R15") (pin "1") (pinfunction "1_1") (pintype "passive"))
      (node (ref "R21") (pin "1") (pinfunction "1_1") (pintype "passive"))
      (node (ref "R22") (pin "1") (pinfunction "1_1") (pintype "passive"))
      (node (ref "R25") (pin "1") (pinfunction "1_1") (pintype "passive"))
      (node (ref "R8") (pin "1") (pinfunction "1_1") (pintype "passive"))
      (node (ref "SWD") (pin "1") (pinfunction "1_1") (pintype "passive"))
      (node (ref "U1") (pin "2") (pinfunction "VSS_2") (pintype "passive"))
      (node (ref "U1") (pin "33") (pinfunction "PAD_33") (pintype "passive"))
      (node (ref "U1") (pin "8") (pinfunction "VSSA_8") (pintype "passive"))
      (node (ref "U2") (pin "1") (pinfunction "GND_1") (pintype "passive"))
      (node (ref "U2") (pin "2") (pinfunction "PAD_2") (pintype "passive"))
      (node (ref "U2") (pin "21") (pinfunction "GND_21") (pintype "passive"))
      (node (ref "U2") (pin "3") (pinfunction "PAD_3") (pintype "passive"))
      (node (ref "U2") (pin "33") (pinfunction "PAD_33") (pintype "passive"))
      (node (ref "U2") (pin "4") (pinfunction "PAD_4") (pintype "passive"))
      (node (ref "U2") (pin "5") (pinfunction "PAD_5") (pintype "passive"))
      (node (ref "U2") (pin "6") (pinfunction "PAD_6") (pintype "passive"))
      (node (ref "U2") (pin "7") (pinfunction "PAD_7") (pintype "passive"))
      (node (ref "U2") (pin "8") (pinfunction "PAD_8") (pintype "passive"))
      (node (ref "U3") (pin "1") (pinfunction "GND_1") (pintype "passive"))
      (node (ref "U3") (pin "2") (pinfunction "PAD_2") (pintype "passive"))
      (node (ref "U3") (pin "21") (pinfunction "GND_21") (pintype "passive"))
      (node (ref "U3") (pin "3") (pinfunction "PAD_3") (pintype "passive"))
      (node (ref "U3") (pin "33") (pinfunction "PAD_33") (pintype "passive"))
      (node (ref "U3") (pin "4") (pinfunction "PAD_4") (pintype "passive"))
      (node (ref "U3") (pin "5") (pinfunction "PAD_5") (pintype "passive"))
      (node (ref "U3") (pin "6") (pinfunction "PAD_6") (pintype "passive"))
      (node (ref "U3") (pin "7") (pinfunction "PAD_7") (pintype "passive"))
      (node (ref "U3") (pin "8") (pinfunction "PAD_8") (pintype "passive"))
      (node (ref "U4") (pin "5") (pinfunction "GND_5") (pintype "power_in"))
      (node (ref "U4") (pin "9") (pinfunction "PAD_9") (pintype "power_in"))
      (node (ref "U7") (pin "1") (pinfunction "A0_1") (pintype "power_in"))
      (node (ref "U7") (pin "2") (pinfunction "A1_2") (pintype "power_in"))
      (node (ref "U7") (pin "3") (pinfunction "A2_3") (pintype "power_in"))
      (node (ref "U7") (pin "4") (pinfunction "VSS_4") (pintype "power_in"))
      (node (ref "U7") (pin "7") (pinfunction "WP_7") (pintype "power_in"))
    )
    (net (code "45") (name "Net-(D1-C)") (class "Default")
      (node (ref "C1") (pin "1") (pinfunction "1_1") (pintype "passive"))
      (node (ref "D1") (pin "3") (pinfunction "C_3") (pintype "passive"))
    )
    (net (code "46") (name "Net-(D1-K)") (class "Default")
      (node (ref "C2") (pin "1") (pinfunction "1_1") (pintype "passive"))
      (node (ref "D1") (pin "2") (pinfunction "K_2") (pintype "passive"))
      (node (ref "U2") (pin "17") (pinfunction "VBOOT_17") (pintype "passive"))
    )
    (net (code "47") (name "Net-(D2-C)") (class "Default")
      (node (ref "C3") (pin "1") (pinfunction "1_1") (pintype "passive"))
      (node (ref "D2") (pin "3") (pinfunction "C_3") (pintype "passive"))
    )
    (net (code "48") (name "Net-(D2-K)") (class "Default")
      (node (ref "C4") (pin "1") (pinfunction "1_1") (pintype "passive"))
      (node (ref "D2") (pin "2") (pinfunction "K_2") (pintype "passive"))
      (node (ref "U3") (pin "17") (pinfunction "VBOOT_17") (pintype "passive"))
    )
    (net (code "49") (name "Net-(LED1-BLUE)") (class "Default")
      (node (ref "LED1") (pin "4") (pinfunction "BLUE_4") (pintype "passive"))
      (node (ref "R11") (pin "2") (pinfunction "2_2") (pintype "passive"))
    )
    (net (code "50") (name "Net-(LED1-GREEN)") (class "Default")
      (node (ref "LED1") (pin "3") (pinfunction "GREEN_3") (pintype "passive"))
      (node (ref "R12") (pin "2") (pinfunction "2_2") (pintype "passive"))
    )
    (net (code "51") (name "Net-(LED1-RED)") (class "Default")
      (node (ref "LED1") (pin "2") (pinfunction "RED_2") (pintype "passive"))
      (node (ref "R14") (pin "2") (pinfunction "2_2") (pintype "passive"))
    )
    (net (code "52") (name "Net-(P1-Pad8)") (class "Default")
      (node (ref "P1") (pin "8") (pinfunction "8_8") (pintype "passive"))
      (node (ref "R1") (pin "1") (pinfunction "1_1") (pintype "passive"))
      (node (ref "R23") (pin "1") (pinfunction "1_1") (pintype "passive"))
    )
    (net (code "53") (name "Net-(P1-Pad10)") (class "Default")
      (node (ref "P1") (pin "10") (pinfunction "10_10") (pintype "passive"))
      (node (ref "R24") (pin "1") (pinfunction "1_1") (pintype "passive"))
      (node (ref "R25") (pin "2") (pinfunction "2_2") (pintype "passive"))
    )
    (net (code "54") (name "Net-(U2-RCOFF)") (class "Default")
      (node (ref "C11") (pin "2") (pinfunction "2_2") (pintype "passive"))
      (node (ref "R8") (pin "2") (pinfunction "2_2") (pintype "passive"))
      (node (ref "U2") (pin "30") (pinfunction "RCOFF_30") (pintype "passive"))
    )
    (net (code "55") (name "Net-(U2-VCP)") (class "Default")
      (node (ref "C1") (pin "2") (pinfunction "2_2") (pintype "passive"))
      (node (ref "U2") (pin "24") (pinfunction "VCP_24") (pintype "passive"))
    )
    (net (code "56") (name "Net-(U3-RCOFF)") (class "Default")
      (node (ref "C14") (pin "2") (pinfunction "2_2") (pintype "passive"))
      (node (ref "R15") (pin "2") (pinfunction "2_2") (pintype "passive"))
      (node (ref "U3") (pin "30") (pinfunction "RCOFF_30") (pintype "passive"))
    )
    (net (code "57") (name "Net-(U3-VCP)") (class "Default")
      (node (ref "C3") (pin "2") (pinfunction "2_2") (pintype "passive"))
      (node (ref "U3") (pin "24") (pinfunction "VCP_24") (pintype "passive"))
    )
    (net (code "58") (name "VM") (class "Default")
      (node (ref "C2") (pin "2") (pinfunction "2_2") (pintype "passive"))
      (node (ref "C4") (pin "2") (pinfunction "2_2") (pintype "passive"))
      (node (ref "D1") (pin "1") (pinfunction "A_1") (pintype "passive"))
      (node (ref "D2") (pin "1") (pinfunction "A_1") (pintype "passive"))
      (node (ref "P1") (pin "1") (pinfunction "1_1") (pintype "passive"))
      (node (ref "U2") (pin "20") (pinfunction "VSB_20") (pintype "passive"))
      (node (ref "U2") (pin "22") (pinfunction "VSA_22") (pintype "passive"))
      (node (ref "U3") (pin "20") (pinfunction "VSB_20") (pintype "passive"))
      (node (ref "U3") (pin "22") (pinfunction "VSA_22") (pintype "passive"))
    )
    (net (code "59") (name "unconnected-(M1-Pad9)") (class "Default")
      (node (ref "M1") (pin "9") (pinfunction "9_9") (pintype "passive"))
    )
    (net (code "60") (name "unconnected-(M1-Pad10)") (class "Default")
      (node (ref "M1") (pin "10") (pinfunction "10_10") (pintype "passive"))
    )
    (net (code "61") (name "unconnected-(M2-Pad9)") (class "Default")
      (node (ref "M2") (pin "9") (pinfunction "9_9") (pintype "passive"))
    )
    (net (code "62") (name "unconnected-(M2-Pad10)") (class "Default")
      (node (ref "M2") (pin "10") (pinfunction "10_10") (pintype "passive"))
    )
    (net (code "63") (name "unconnected-(U1-PTB1-Pad21)") (class "Default")
      (node (ref "U1") (pin "21") (pinfunction "PTB1_21") (pintype "passive"))
    )
    (net (code "64") (name "unconnected-(U2-NC-Pad10)") (class "Default")
      (node (ref "U2") (pin "10") (pinfunction "NC_10") (pintype "passive"))
    )
    (net (code "65") (name "unconnected-(U2-NC-Pad18)") (class "Default")
      (node (ref "U2") (pin "18") (pinfunction "NC_18") (pintype "passive"))
    )
    (net (code "66") (name "unconnected-(U2-NC-Pad32)") (class "Default")
      (node (ref "U2") (pin "32") (pinfunction "NC_32") (pintype "passive"))
    )
    (net (code "67") (name "unconnected-(U2-RCPULSE-Pad11)") (class "Default")
      (node (ref "U2") (pin "11") (pinfunction "RCPULSE_11") (pintype "passive"))
    )
    (net (code "68") (name "unconnected-(U3-NC-Pad10)") (class "Default")
      (node (ref "U3") (pin "10") (pinfunction "NC_10") (pintype "passive"))
    )
    (net (code "69") (name "unconnected-(U3-NC-Pad18)") (class "Default")
      (node (ref "U3") (pin "18") (pinfunction "NC_18") (pintype "passive"))
    )
    (net (code "70") (name "unconnected-(U3-NC-Pad32)") (class "Default")
      (node (ref "U3") (pin "32") (pinfunction "NC_32") (pintype "passive"))
    )
    (net (code "71") (name "unconnected-(U3-RCPULSE-Pad11)") (class "Default")
      (node (ref "U3") (pin "11") (pinfunction "RCPULSE_11") (pintype "passive"))
    )
  )
)
